# Power.net
KiCad netlist of a schematic drawn in Altium Designer
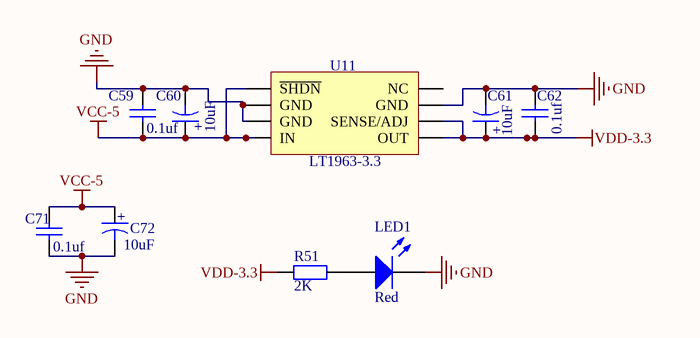
[diagram p0: Power.SchDoc]

(export (version "E")
  (design (tool "Eeschema 10.0.6"))
  (components
    (comp (ref "C59")
      (value "0.1uf")
      (footprint "0805")
      (fields (field (name "Comment") "Capacitor-0805"))
      (libsource (lib "集成库—大岐") (part "Capacitor-0805"))
    )
    (comp (ref "C60")
      (value "10uF")
      (footprint "钽电容1206（A3216）")
      (fields (field (name "ALTIUM_UNNAMED_1") "+") (field (name "Comment") "电解电容"))
      (libsource (lib "集成库—大岐") (part "电解电容"))
    )
    (comp (ref "C61")
      (value "10uF")
      (footprint "钽电容1206（A3216）")
      (fields (field (name "ALTIUM_UNNAMED_1") "+") (field (name "Comment") "电解电容"))
      (libsource (lib "集成库—大岐") (part "电解电容"))
    )
    (comp (ref "C62")
      (value "0.1uf")
      (footprint "0805")
      (fields (field (name "Comment") "Capacitor-0805"))
      (libsource (lib "集成库—大岐") (part "Capacitor-0805"))
    )
    (comp (ref "C71")
      (value "0.1uf")
      (footprint "0805")
      (fields (field (name "Comment") "Capacitor-0805"))
      (libsource (lib "集成库—大岐") (part "Capacitor-0805"))
    )
    (comp (ref "C72")
      (value "10uF")
      (footprint "钽电容1206（A3216）")
      (fields (field (name "ALTIUM_UNNAMED_1") "+") (field (name "Comment") "电解电容"))
      (libsource (lib "集成库—大岐") (part "电解电容"))
    )
    (comp (ref "LED1")
      (value "LED")
      (footprint "LED-0805")
      (fields (field (name "COLOR") "Red"))
      (libsource (lib "原理图库") (part "LED"))
    )
    (comp (ref "R51")
      (value "2K")
      (footprint "0603")
      (fields (field (name "Comment") "Resistor-0603"))
      (libsource (lib "原理图库") (part "Resistor-0603"))
    )
    (comp (ref "U11")
      (value "LT1963")
      (footprint "LT1963")
      (fields (field (name "ALTIUM_UNNAMED_1") "LT1963-3.3"))
      (libsource (lib "集成库—大岐") (part "LT1963"))
    )
  )
  (nets
    (net (code "1") (name "GND") (class "Default")
      (node (ref "C59") (pin "2") (pinfunction "2_2") (pintype "passive"))
      (node (ref "C60") (pin "1") (pinfunction "1_1") (pintype "passive"))
      (node (ref "C61") (pin "1") (pinfunction "1_1") (pintype "passive"))
      (node (ref "C62") (pin "2") (pinfunction "2_2") (pintype "passive"))
      (node (ref "C71") (pin "1") (pinfunction "1_1") (pintype "passive"))
      (node (ref "C72") (pin "1") (pinfunction "1_1") (pintype "passive"))
      (node (ref "LED1") (pin "2") (pinfunction "2_2") (pintype "passive"))
      (node (ref "U11") (pin "3") (pinfunction "GND_3") (pintype "passive"))
      (node (ref "U11") (pin "6") (pinfunction "GND_6") (pintype "passive"))
      (node (ref "U11") (pin "7") (pinfunction "GND_7") (pintype "passive"))
    )
    (net (code "2") (name "Net-(LED1-A)") (class "Default")
      (node (ref "LED1") (pin "1") (pinfunction "A_1") (pintype "passive"))
      (node (ref "R51") (pin "1") (pinfunction "1_1") (pintype "passive"))
    )
    (net (code "3") (name "VCC-5") (class "Default")
      (node (ref "C59") (pin "1") (pinfunction "1_1") (pintype "passive"))
      (node (ref "C60") (pin "2") (pinfunction "2_2") (pintype "passive"))
      (node (ref "C71") (pin "2") (pinfunction "2_2") (pintype "passive"))
      (node (ref "C72") (pin "2") (pinfunction "2_2") (pintype "passive"))
      (node (ref "U11") (pin "5") (pinfunction "~{SHDN}_5") (pintype "passive"))
      (node (ref "U11") (pin "8") (pinfunction "IN_8") (pintype "passive"))
    )
    (net (code "4") (name "VDD-3.3") (class "Default")
      (node (ref "C61") (pin "2") (pinfunction "2_2") (pintype "passive"))
      (node (ref "C62") (pin "1") (pinfunction "1_1") (pintype "passive"))
      (node (ref "R51") (pin "2") (pinfunction "2_2") (pintype "passive"))
      (node (ref "U11") (pin "1") (pinfunction "OUT_1") (pintype "passive"))
      (node (ref "U11") (pin "2") (pinfunction "SENSE/ADJ_2") (pintype "passive"))
    )
    (net (code "5") (name "unconnected-(U11-NC-Pad4)") (class "Default")
      (node (ref "U11") (pin "4") (pinfunction "NC_4") (pintype "passive"))
    )
  )
)
